# 00A-001.net
KiCad netlist of a schematic drawn in EAGLE
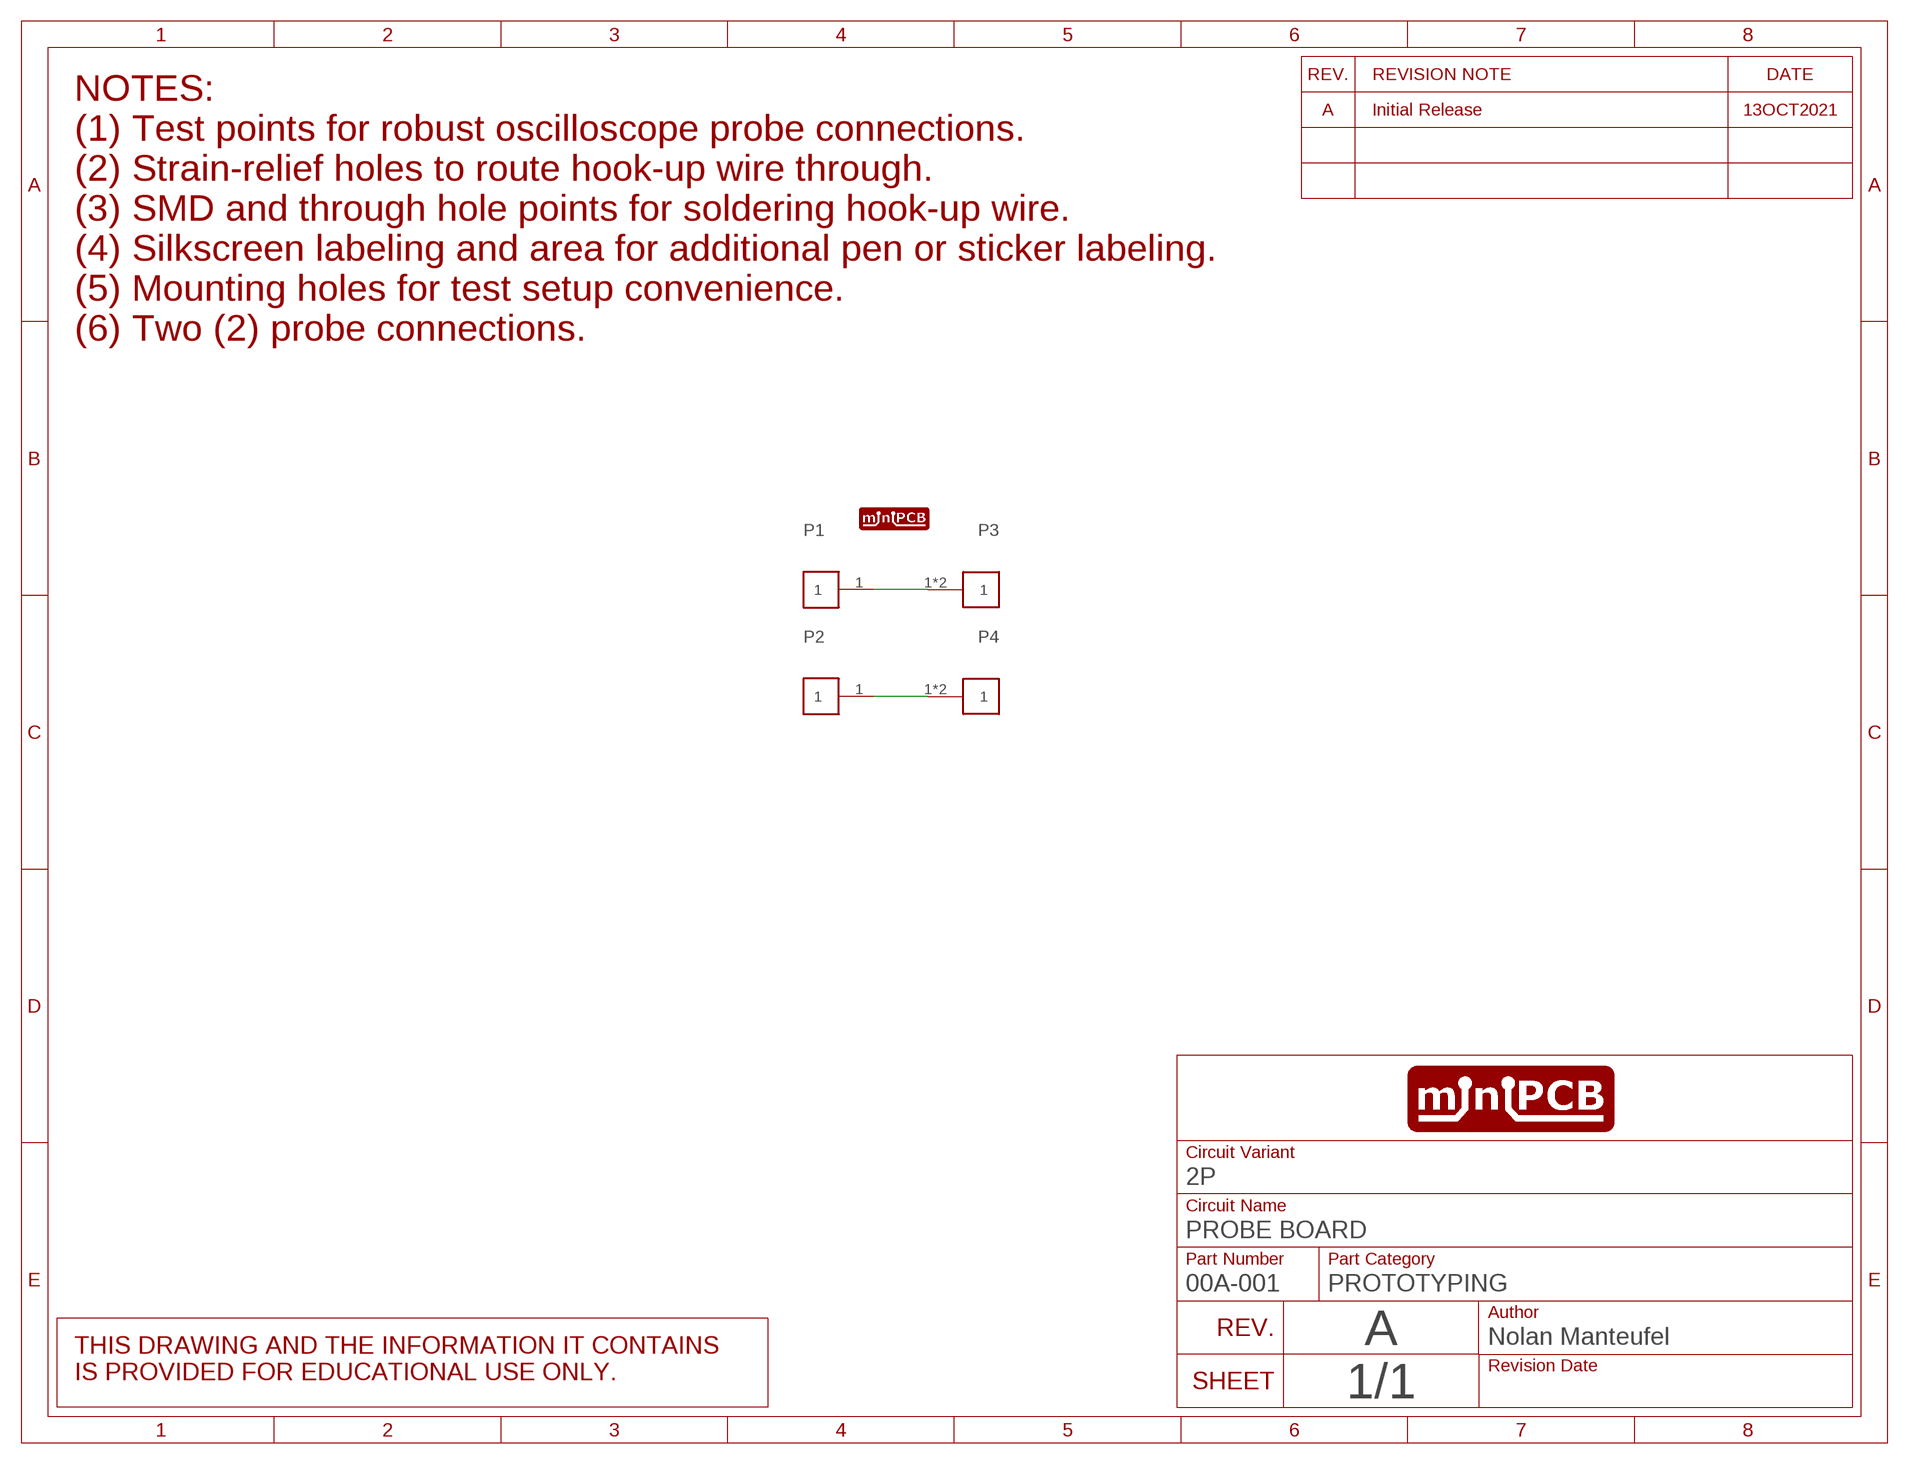
[diagram p0: schematic, sheet 1]

(export (version "E")
  (design (tool "Eeschema 10.0.6"))
  (components
    (comp (ref "P1")
      (value "PINS_1KE_5000")
      (footprint "eagle-import:PINS_1_TESTPOINT_KE5000")
      (libsource (lib "eagle-import") (part "PINS_1KE_5000"))
    )
    (comp (ref "P2")
      (value "PINS_1KE_5000")
      (footprint "eagle-import:PINS_1_TESTPOINT_KE5000")
      (libsource (lib "eagle-import") (part "PINS_1KE_5000"))
    )
    (comp (ref "P3")
      (value "PINS_124AWG")
      (footprint "eagle-import:PINS_1_1MM")
      (libsource (lib "eagle-import") (part "PINS_124AWG"))
    )
    (comp (ref "P4")
      (value "PINS_124AWG")
      (footprint "eagle-import:PINS_1_1MM")
      (libsource (lib "eagle-import") (part "PINS_124AWG"))
    )
    (comp (ref "U$1")
      (value "MINIPCB_LOGO")
      (footprint "eagle-import:MINIPCB-LOGO")
      (libsource (lib "eagle-import") (part "MINIPCB_LOGO"))
    )
  )
  (nets
    (net (code "1") (name "Net-(P1-Pad1)") (class "Default")
      (node (ref "P1") (pin "1") (pinfunction "1_1") (pintype "bidirectional"))
      (node (ref "P3") (pin "1") (pinfunction "1_1") (pintype "bidirectional"))
      (node (ref "P3") (pin "2") (pinfunction "1_2") (pintype "bidirectional"))
    )
    (net (code "2") (name "Net-(P2-Pad1)") (class "Default")
      (node (ref "P2") (pin "1") (pinfunction "1_1") (pintype "bidirectional"))
      (node (ref "P4") (pin "1") (pinfunction "1_1") (pintype "bidirectional"))
      (node (ref "P4") (pin "2") (pinfunction "1_2") (pintype "bidirectional"))
    )
  )
)
